# MAX78630_SOC.net
KiCad netlist of a schematic drawn in Altium Designer
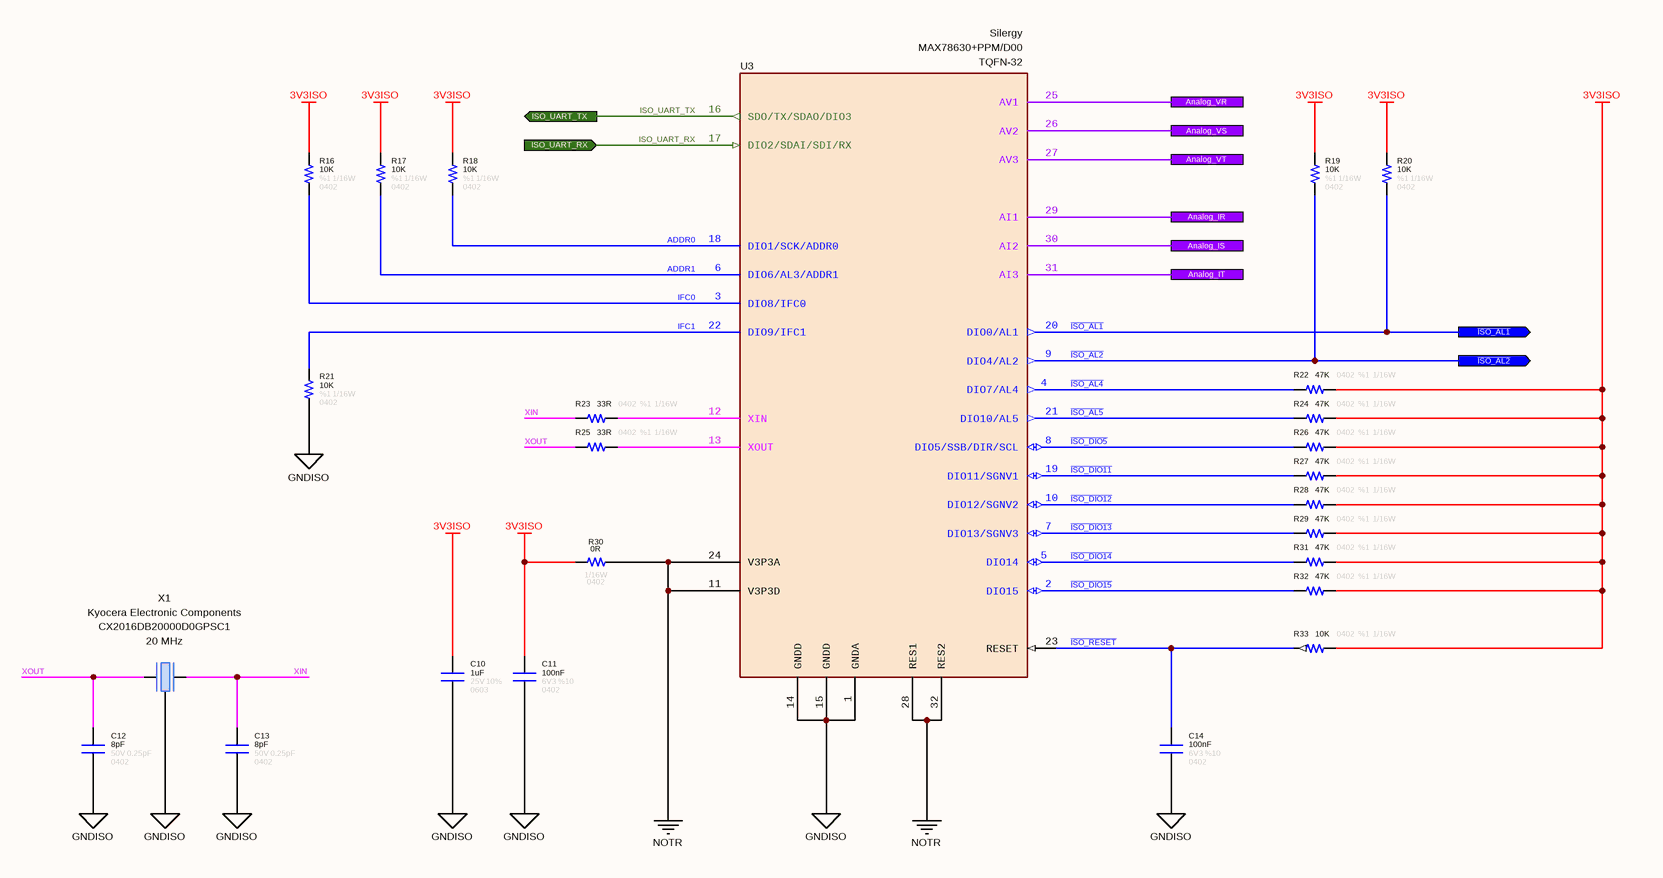
[diagram p0: MAX78630 SOC.SchDoc]

(export (version "E")
  (design (tool "Eeschema 10.0.6"))
  (components
    (comp (ref "C10")
      (value "1uF")
      (footprint "CAPACITOR_0603")
      (description "Capacitor (MLCC) - 1uF / 25V / 0603")
      (fields
        (field (name "MANUFACTURER PART NUMBER") "GCJ188R71E105KA01D")
        (field (name "TOLERANCE") "10%")
        (field (name "CASE") "0603")
        (field (name "VOLTAGE") "25V")
        (field (name "Comment") "Capacitor - 1uF [0603] (MLCC)")
      )
      (libsource (lib "Akkoyun") (part "Capacitor - 1uF [0603-25V]"))
    )
    (comp (ref "C11")
      (value "100nF")
      (footprint "CAPACITOR_0402")
      (description "Capacitor - 100nF [0402-6V3] (Ceramic)")
      (fields
        (field (name "MANUFACTURER PART NUMBER") "04026D104KAT4A")
        (field (name "TOLERANCE") "%10")
        (field (name "VOLTAGE") "6V3")
        (field (name "CASE") "0402")
        (field (name "Comment") "Capacitor - 100nF [0402] (Ceramic)")
      )
      (libsource (lib "Akkoyun") (part "Capacitor - 100nF [0402-6V3]"))
    )
    (comp (ref "C12")
      (value "8pF")
      (footprint "CAPACITOR_0402")
      (description "Capacitor - 8pF [0402] (Ceramic)")
      (fields
        (field (name "MANUFACTURER PART NUMBER") "04025A8R0CAT2A")
        (field (name "TOLERANCE") "0.25pF")
        (field (name "CASE") "0402")
        (field (name "VOLTAGE") "50V")
      )
      (libsource (lib "Akkoyun") (part "Capacitor - 8pF [0402-50V]"))
    )
    (comp (ref "C13")
      (value "8pF")
      (footprint "CAPACITOR_0402")
      (description "Capacitor - 8pF [0402] (Ceramic)")
      (fields
        (field (name "MANUFACTURER PART NUMBER") "04025A8R0CAT2A")
        (field (name "TOLERANCE") "0.25pF")
        (field (name "CASE") "0402")
        (field (name "VOLTAGE") "50V")
      )
      (libsource (lib "Akkoyun") (part "Capacitor - 8pF [0402-50V]"))
    )
    (comp (ref "C14")
      (value "100nF")
      (footprint "CAPACITOR_0402")
      (description "Capacitor - 100nF [0402-6V3] (Ceramic)")
      (fields
        (field (name "MANUFACTURER PART NUMBER") "04026D104KAT4A")
        (field (name "TOLERANCE") "%10")
        (field (name "VOLTAGE") "6V3")
        (field (name "CASE") "0402")
        (field (name "Comment") "Capacitor - 100nF [0402] (Ceramic)")
      )
      (libsource (lib "Akkoyun") (part "Capacitor - 100nF [0402-6V3]"))
    )
    (comp (ref "R16")
      (value "10K")
      (footprint "RESISTOR_0402")
      (description "Thick Film Resistors - SMD 1/16 W 10 KOhm 1%")
      (fields
        (field (name "MANUFACTURER PART NUMBER") "CRCW040210K0FKED")
        (field (name "TOLERANCE") "%1")
        (field (name "CASE") "0402")
        (field (name "POWER") "1/16W")
        (field (name "Comment") "10K - 0402 - %1 - 1/16W")
      )
      (libsource (lib "Akkoyun") (part "Resistor - 10K [0402]"))
    )
    (comp (ref "R17")
      (value "10K")
      (footprint "RESISTOR_0402")
      (description "Thick Film Resistors - SMD 1/16 W 10 KOhm 1%")
      (fields
        (field (name "MANUFACTURER PART NUMBER") "CRCW040210K0FKED")
        (field (name "TOLERANCE") "%1")
        (field (name "CASE") "0402")
        (field (name "POWER") "1/16W")
        (field (name "Comment") "10K - 0402 - %1 - 1/16W")
      )
      (libsource (lib "Akkoyun") (part "Resistor - 10K [0402]"))
    )
    (comp (ref "R18")
      (value "10K")
      (footprint "RESISTOR_0402")
      (description "Thick Film Resistors - SMD 1/16 W 10 KOhm 1%")
      (fields
        (field (name "MANUFACTURER PART NUMBER") "CRCW040210K0FKED")
        (field (name "TOLERANCE") "%1")
        (field (name "CASE") "0402")
        (field (name "POWER") "1/16W")
        (field (name "Comment") "10K - 0402 - %1 - 1/16W")
      )
      (libsource (lib "Akkoyun") (part "Resistor - 10K [0402]"))
    )
    (comp (ref "R19")
      (value "10K")
      (footprint "RESISTOR_0402")
      (description "Thick Film Resistors - SMD 1/16 W 10 KOhm 1%")
      (fields
        (field (name "MANUFACTURER PART NUMBER") "CRCW040210K0FKED")
        (field (name "TOLERANCE") "%1")
        (field (name "CASE") "0402")
        (field (name "POWER") "1/16W")
        (field (name "Comment") "10K - 0402 - %1 - 1/16W")
      )
      (libsource (lib "Akkoyun") (part "Resistor - 10K [0402]"))
    )
    (comp (ref "R20")
      (value "10K")
      (footprint "RESISTOR_0402")
      (description "Thick Film Resistors - SMD 1/16 W 10 KOhm 1%")
      (fields
        (field (name "MANUFACTURER PART NUMBER") "CRCW040210K0FKED")
        (field (name "TOLERANCE") "%1")
        (field (name "CASE") "0402")
        (field (name "POWER") "1/16W")
        (field (name "Comment") "10K - 0402 - %1 - 1/16W")
      )
      (libsource (lib "Akkoyun") (part "Resistor - 10K [0402]"))
    )
    (comp (ref "R21")
      (value "10K")
      (footprint "RESISTOR_0402")
      (description "Thick Film Resistors - SMD 1/16 W 10 KOhm 1%")
      (fields
        (field (name "MANUFACTURER PART NUMBER") "CRCW040210K0FKED")
        (field (name "TOLERANCE") "%1")
        (field (name "CASE") "0402")
        (field (name "POWER") "1/16W")
        (field (name "Comment") "10K - 0402 - %1 - 1/16W")
      )
      (libsource (lib "Akkoyun") (part "Resistor - 10K [0402]"))
    )
    (comp (ref "R22")
      (value "47K")
      (footprint "RESISTOR_0402")
      (description "Thick Film Resistors - SMD 1/16 W 47 KOhm 1%")
      (fields
        (field (name "MANUFACTURER PART NUMBER") "CRCW040247K0FKED")
        (field (name "TOLERANCE") "%1")
        (field (name "CASE") "0402")
        (field (name "POWER") "1/16W")
        (field (name "Comment") "47K - 0402 - %1 - 1/16W")
      )
      (libsource (lib "Akkoyun") (part "Resistor - 47K [0402]"))
    )
    (comp (ref "R23")
      (value "33R")
      (footprint "RESISTOR_0402")
      (description "Thick Film Resistors - SMD 1/16 W 33 Ohm 1%")
      (fields
        (field (name "MANUFACTURER PART NUMBER") "CRCW040233R0FKED")
        (field (name "CASE") "0402")
        (field (name "TOLERANCE") "%1")
        (field (name "POWER") "1/16W")
        (field (name "Comment") "33R - 0402 - %1 - 1/16W")
      )
      (libsource (lib "Akkoyun") (part "Resistor - 33R [0402]"))
    )
    (comp (ref "R24")
      (value "47K")
      (footprint "RESISTOR_0402")
      (description "Thick Film Resistors - SMD 1/16 W 47 KOhm 1%")
      (fields
        (field (name "MANUFACTURER PART NUMBER") "CRCW040247K0FKED")
        (field (name "TOLERANCE") "%1")
        (field (name "CASE") "0402")
        (field (name "POWER") "1/16W")
        (field (name "Comment") "47K - 0402 - %1 - 1/16W")
      )
      (libsource (lib "Akkoyun") (part "Resistor - 47K [0402]"))
    )
    (comp (ref "R25")
      (value "33R")
      (footprint "RESISTOR_0402")
      (description "Thick Film Resistors - SMD 1/16 W 33 Ohm 1%")
      (fields
        (field (name "MANUFACTURER PART NUMBER") "CRCW040233R0FKED")
        (field (name "CASE") "0402")
        (field (name "TOLERANCE") "%1")
        (field (name "POWER") "1/16W")
        (field (name "Comment") "33R - 0402 - %1 - 1/16W")
      )
      (libsource (lib "Akkoyun") (part "Resistor - 33R [0402]"))
    )
    (comp (ref "R26")
      (value "47K")
      (footprint "RESISTOR_0402")
      (description "Thick Film Resistors - SMD 1/16 W 47 KOhm 1%")
      (fields
        (field (name "MANUFACTURER PART NUMBER") "CRCW040247K0FKED")
        (field (name "TOLERANCE") "%1")
        (field (name "CASE") "0402")
        (field (name "POWER") "1/16W")
        (field (name "Comment") "47K - 0402 - %1 - 1/16W")
      )
      (libsource (lib "Akkoyun") (part "Resistor - 47K [0402]"))
    )
    (comp (ref "R27")
      (value "47K")
      (footprint "RESISTOR_0402")
      (description "Thick Film Resistors - SMD 1/16 W 47 KOhm 1%")
      (fields
        (field (name "MANUFACTURER PART NUMBER") "CRCW040247K0FKED")
        (field (name "TOLERANCE") "%1")
        (field (name "CASE") "0402")
        (field (name "POWER") "1/16W")
        (field (name "Comment") "47K - 0402 - %1 - 1/16W")
      )
      (libsource (lib "Akkoyun") (part "Resistor - 47K [0402]"))
    )
    (comp (ref "R28")
      (value "47K")
      (footprint "RESISTOR_0402")
      (description "Thick Film Resistors - SMD 1/16 W 47 KOhm 1%")
      (fields
        (field (name "MANUFACTURER PART NUMBER") "CRCW040247K0FKED")
        (field (name "TOLERANCE") "%1")
        (field (name "CASE") "0402")
        (field (name "POWER") "1/16W")
        (field (name "Comment") "47K - 0402 - %1 - 1/16W")
      )
      (libsource (lib "Akkoyun") (part "Resistor - 47K [0402]"))
    )
    (comp (ref "R29")
      (value "47K")
      (footprint "RESISTOR_0402")
      (description "Thick Film Resistors - SMD 1/16 W 47 KOhm 1%")
      (fields
        (field (name "MANUFACTURER PART NUMBER") "CRCW040247K0FKED")
        (field (name "TOLERANCE") "%1")
        (field (name "CASE") "0402")
        (field (name "POWER") "1/16W")
        (field (name "Comment") "47K - 0402 - %1 - 1/16W")
      )
      (libsource (lib "Akkoyun") (part "Resistor - 47K [0402]"))
    )
    (comp (ref "R30")
      (value "0R")
      (footprint "RESISTOR_0402")
      (description "Thick Film Resistors - SMD 1/16 W 0 Ohm")
      (fields
        (field (name "MANUFACTURER PART NUMBER") "CRCW04020000Z0ED")
        (field (name "CASE") "0402")
        (field (name "POWER") "1/16W")
        (field (name "Comment") "0R - 0402 - %1 - 1/16W")
      )
      (libsource (lib "Akkoyun") (part "Resistor - 0R [0402]"))
    )
    (comp (ref "R31")
      (value "47K")
      (footprint "RESISTOR_0402")
      (description "Thick Film Resistors - SMD 1/16 W 47 KOhm 1%")
      (fields
        (field (name "MANUFACTURER PART NUMBER") "CRCW040247K0FKED")
        (field (name "TOLERANCE") "%1")
        (field (name "CASE") "0402")
        (field (name "POWER") "1/16W")
        (field (name "Comment") "47K - 0402 - %1 - 1/16W")
      )
      (libsource (lib "Akkoyun") (part "Resistor - 47K [0402]"))
    )
    (comp (ref "R32")
      (value "47K")
      (footprint "RESISTOR_0402")
      (description "Thick Film Resistors - SMD 1/16 W 47 KOhm 1%")
      (fields
        (field (name "MANUFACTURER PART NUMBER") "CRCW040247K0FKED")
        (field (name "TOLERANCE") "%1")
        (field (name "CASE") "0402")
        (field (name "POWER") "1/16W")
        (field (name "Comment") "47K - 0402 - %1 - 1/16W")
      )
      (libsource (lib "Akkoyun") (part "Resistor - 47K [0402]"))
    )
    (comp (ref "R33")
      (value "10K")
      (footprint "RESISTOR_0402")
      (description "Thick Film Resistors - SMD 1/16 W 10 KOhm 1%")
      (fields
        (field (name "MANUFACTURER PART NUMBER") "CRCW040210K0FKED")
        (field (name "TOLERANCE") "%1")
        (field (name "CASE") "0402")
        (field (name "POWER") "1/16W")
        (field (name "Comment") "10K - 0402 - %1 - 1/16W")
      )
      (libsource (lib "Akkoyun") (part "Resistor - 10K [0402]"))
    )
    (comp (ref "U3")
      (value "MAX78630+PPM/D00")
      (footprint "TQFN-32 - Maxim")
      (description "Energy Measurement Processor 32-Pin TQFN EP Tube")
      (fields
        (field (name "MANUFACTURER NAME") "Silergy")
        (field (name "MANUFACTURER PART NUMBER") "MAX78630+PPM/D00")
        (field (name "CASE") "TQFN-32")
      )
      (libsource (lib "Akkoyun") (part "IC - MAX78630"))
    )
    (comp (ref "X1")
      (value "CX2016DB20000D0GPSC1")
      (footprint "CRYSTAL - 20MHz")
      (description "Crystals AEC-Q200 20000kHz 8pF 2x1.6mm")
      (fields
        (field (name "MANUFACTURER NAME") "Kyocera Electronic Components")
        (field (name "MANUFACTURER PART NUMBER") "CX2016DB20000D0GPSC1")
        (field (name "FREQUENCY") "20 MHz")
      )
      (libsource (lib "Akkoyun") (part "Crystal - 20MHz"))
    )
  )
  (nets
    (net (code "1") (name "/ADDR0") (class "Default")
      (node (ref "R18") (pin "1") (pinfunction "1_1") (pintype "passive"))
      (node (ref "U3") (pin "18") (pinfunction "DIO1/SCK/ADDR0_18") (pintype "passive"))
    )
    (net (code "2") (name "/ADDR1") (class "Default")
      (node (ref "R17") (pin "1") (pinfunction "1_1") (pintype "passive"))
      (node (ref "U3") (pin "6") (pinfunction "DIO6/AL3/ADDR1_6") (pintype "passive"))
    )
    (net (code "3") (name "/Analog_IR") (class "Default")
      (node (ref "U3") (pin "29") (pinfunction "AI1_29") (pintype "passive"))
    )
    (net (code "4") (name "/Analog_IS") (class "Default")
      (node (ref "U3") (pin "30") (pinfunction "AI2_30") (pintype "passive"))
    )
    (net (code "5") (name "/Analog_IT") (class "Default")
      (node (ref "U3") (pin "31") (pinfunction "AI3_31") (pintype "passive"))
    )
    (net (code "6") (name "/Analog_VR") (class "Default")
      (node (ref "U3") (pin "25") (pinfunction "AV1_25") (pintype "passive"))
    )
    (net (code "7") (name "/Analog_VS") (class "Default")
      (node (ref "U3") (pin "26") (pinfunction "AV2_26") (pintype "passive"))
    )
    (net (code "8") (name "/Analog_VT") (class "Default")
      (node (ref "U3") (pin "27") (pinfunction "AV3_27") (pintype "passive"))
    )
    (net (code "9") (name "/IFC0") (class "Default")
      (node (ref "R16") (pin "1") (pinfunction "1_1") (pintype "passive"))
      (node (ref "U3") (pin "3") (pinfunction "DIO8/IFC0_3") (pintype "passive"))
    )
    (net (code "10") (name "/IFC1") (class "Default")
      (node (ref "R21") (pin "2") (pinfunction "2_2") (pintype "passive"))
      (node (ref "U3") (pin "22") (pinfunction "DIO9/IFC1_22") (pintype "passive"))
    )
    (net (code "11") (name "/ISO_UART_RX") (class "Default")
      (node (ref "U3") (pin "17") (pinfunction "DIO2/SDAI/SDI/RX_17") (pintype "input"))
    )
    (net (code "12") (name "/ISO_UART_TX") (class "Default")
      (node (ref "U3") (pin "16") (pinfunction "SDO/TX/SDAO/DIO3_16") (pintype "output"))
    )
    (net (code "13") (name "/XIN") (class "Default")
      (node (ref "C13") (pin "2") (pinfunction "2_2") (pintype "passive"))
      (node (ref "R23") (pin "2") (pinfunction "2_2") (pintype "passive"))
      (node (ref "X1") (pin "1") (pinfunction "IN/OUT_1") (pintype "passive"))
    )
    (net (code "14") (name "/XOUT") (class "Default")
      (node (ref "C12") (pin "2") (pinfunction "2_2") (pintype "passive"))
      (node (ref "R25") (pin "2") (pinfunction "2_2") (pintype "passive"))
      (node (ref "X1") (pin "3") (pinfunction "OUT/IN_3") (pintype "passive"))
    )
    (net (code "15") (name "/~{ISO_AL1}") (class "Default")
      (node (ref "R20") (pin "1") (pinfunction "1_1") (pintype "passive"))
      (node (ref "U3") (pin "20") (pinfunction "DIO0/AL1_20") (pintype "output"))
    )
    (net (code "16") (name "/~{ISO_AL2}") (class "Default")
      (node (ref "R19") (pin "1") (pinfunction "1_1") (pintype "passive"))
      (node (ref "U3") (pin "9") (pinfunction "DIO4/AL2_9") (pintype "output"))
    )
    (net (code "17") (name "/~{ISO_AL4}") (class "Default")
      (node (ref "R22") (pin "2") (pinfunction "2_2") (pintype "passive"))
      (node (ref "U3") (pin "4") (pinfunction "DIO7/AL4_4") (pintype "output"))
    )
    (net (code "18") (name "/~{ISO_AL5}") (class "Default")
      (node (ref "R24") (pin "2") (pinfunction "2_2") (pintype "passive"))
      (node (ref "U3") (pin "21") (pinfunction "DIO10/AL5_21") (pintype "output"))
    )
    (net (code "19") (name "/~{ISO_DIO5}") (class "Default")
      (node (ref "R26") (pin "2") (pinfunction "2_2") (pintype "passive"))
      (node (ref "U3") (pin "8") (pinfunction "DIO5/SSB/DIR/SCL_8") (pintype "bidirectional"))
    )
    (net (code "20") (name "/~{ISO_DIO11}") (class "Default")
      (node (ref "R27") (pin "2") (pinfunction "2_2") (pintype "passive"))
      (node (ref "U3") (pin "19") (pinfunction "DIO11/SGNV1_19") (pintype "bidirectional"))
    )
    (net (code "21") (name "/~{ISO_DIO12}") (class "Default")
      (node (ref "R28") (pin "2") (pinfunction "2_2") (pintype "passive"))
      (node (ref "U3") (pin "10") (pinfunction "DIO12/SGNV2_10") (pintype "bidirectional"))
    )
    (net (code "22") (name "/~{ISO_DIO13}") (class "Default")
      (node (ref "R29") (pin "2") (pinfunction "2_2") (pintype "passive"))
      (node (ref "U3") (pin "7") (pinfunction "DIO13/SGNV3_7") (pintype "bidirectional"))
    )
    (net (code "23") (name "/~{ISO_DIO14}") (class "Default")
      (node (ref "R31") (pin "2") (pinfunction "2_2") (pintype "passive"))
      (node (ref "U3") (pin "5") (pinfunction "DIO14_5") (pintype "bidirectional"))
    )
    (net (code "24") (name "/~{ISO_DIO15}") (class "Default")
      (node (ref "R32") (pin "2") (pinfunction "2_2") (pintype "passive"))
      (node (ref "U3") (pin "2") (pinfunction "DIO15_2") (pintype "bidirectional"))
    )
    (net (code "25") (name "/~{ISO_RESET}") (class "Default")
      (node (ref "C14") (pin "2") (pinfunction "2_2") (pintype "passive"))
      (node (ref "R33") (pin "2") (pinfunction "2_2") (pintype "passive"))
      (node (ref "U3") (pin "23") (pinfunction "RESET_23") (pintype "input"))
    )
    (net (code "26") (name "3V3ISO") (class "Default")
      (node (ref "C10") (pin "2") (pinfunction "2_2") (pintype "passive"))
      (node (ref "C11") (pin "2") (pinfunction "2_2") (pintype "passive"))
      (node (ref "R16") (pin "2") (pinfunction "2_2") (pintype "passive"))
      (node (ref "R17") (pin "2") (pinfunction "2_2") (pintype "passive"))
      (node (ref "R18") (pin "2") (pinfunction "2_2") (pintype "passive"))
      (node (ref "R19") (pin "2") (pinfunction "2_2") (pintype "passive"))
      (node (ref "R20") (pin "2") (pinfunction "2_2") (pintype "passive"))
      (node (ref "R22") (pin "1") (pinfunction "1_1") (pintype "passive"))
      (node (ref "R24") (pin "1") (pinfunction "1_1") (pintype "passive"))
      (node (ref "R26") (pin "1") (pinfunction "1_1") (pintype "passive"))
      (node (ref "R27") (pin "1") (pinfunction "1_1") (pintype "passive"))
      (node (ref "R28") (pin "1") (pinfunction "1_1") (pintype "passive"))
      (node (ref "R29") (pin "1") (pinfunction "1_1") (pintype "passive"))
      (node (ref "R30") (pin "2") (pinfunction "2_2") (pintype "passive"))
      (node (ref "R31") (pin "1") (pinfunction "1_1") (pintype "passive"))
      (node (ref "R32") (pin "1") (pinfunction "1_1") (pintype "passive"))
      (node (ref "R33") (pin "1") (pinfunction "1_1") (pintype "passive"))
    )
    (net (code "27") (name "GNDISO") (class "Default")
      (node (ref "C10") (pin "1") (pinfunction "1_1") (pintype "passive"))
      (node (ref "C11") (pin "1") (pinfunction "1_1") (pintype "passive"))
      (node (ref "C12") (pin "1") (pinfunction "1_1") (pintype "passive"))
      (node (ref "C13") (pin "1") (pinfunction "1_1") (pintype "passive"))
      (node (ref "C14") (pin "1") (pinfunction "1_1") (pintype "passive"))
      (node (ref "R21") (pin "1") (pinfunction "1_1") (pintype "passive"))
      (node (ref "U3") (pin "1") (pinfunction "GNDA_1") (pintype "power_in"))
      (node (ref "U3") (pin "14") (pinfunction "GNDD_14") (pintype "power_in"))
      (node (ref "U3") (pin "15") (pinfunction "GNDD_15") (pintype "power_in"))
      (node (ref "X1") (pin "2") (pinfunction "GND_2") (pintype "passive"))
    )
    (net (code "28") (name "NOTR") (class "Default")
      (node (ref "R30") (pin "1") (pinfunction "1_1") (pintype "passive"))
      (node (ref "U3") (pin "11") (pinfunction "V3P3D_11") (pintype "power_in"))
      (node (ref "U3") (pin "24") (pinfunction "V3P3A_24") (pintype "power_in"))
      (node (ref "U3") (pin "28") (pinfunction "RES1_28") (pintype "passive"))
      (node (ref "U3") (pin "32") (pinfunction "RES2_32") (pintype "passive"))
    )
    (net (code "29") (name "Net-(U3-XIN)") (class "Default")
      (node (ref "R23") (pin "1") (pinfunction "1_1") (pintype "passive"))
      (node (ref "U3") (pin "12") (pinfunction "XIN_12") (pintype "passive"))
    )
    (net (code "30") (name "Net-(U3-XOUT)") (class "Default")
      (node (ref "R25") (pin "1") (pinfunction "1_1") (pintype "passive"))
      (node (ref "U3") (pin "13") (pinfunction "XOUT_13") (pintype "passive"))
    )
    (net (code "31") (name "unconnected-(X1-GND-Pad4)") (class "Default")
      (node (ref "X1") (pin "4") (pinfunction "GND_4") (pintype "passive"))
    )
  )
)
